# LED.net
KiCad netlist of a schematic drawn in Altium Designer
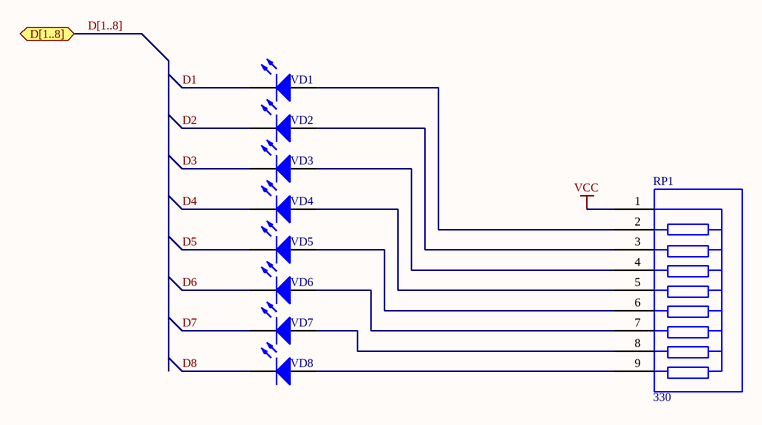
[diagram p0: LED.SchDoc]

(export (version "E")
  (design (tool "Eeschema 10.0.6"))
  (components
    (comp (ref "RP1") (value "330") (footprint "SIP9") (libsource (lib "TEST2024") (part "SIP-A09")))
    (comp (ref "VD1")
      (value "BT101")
      (footprint "LED-5")
      (description "Typical INFRARED GaAs LED")
      (fields (field (name "PUBLISHER") "Altium Limited"))
      (libsource (lib "TEST2024") (part "LED0"))
    )
    (comp (ref "VD2")
      (value "BT101")
      (footprint "LED-5")
      (description "Typical INFRARED GaAs LED")
      (fields (field (name "PUBLISHER") "Altium Limited"))
      (libsource (lib "TEST2024") (part "LED0"))
    )
    (comp (ref "VD3")
      (value "BT101")
      (footprint "LED-5")
      (description "Typical INFRARED GaAs LED")
      (fields (field (name "PUBLISHER") "Altium Limited"))
      (libsource (lib "TEST2024") (part "LED0"))
    )
    (comp (ref "VD4")
      (value "BT101")
      (footprint "LED-5")
      (description "Typical INFRARED GaAs LED")
      (fields (field (name "PUBLISHER") "Altium Limited"))
      (libsource (lib "TEST2024") (part "LED0"))
    )
    (comp (ref "VD5")
      (value "BT101")
      (footprint "LED-5")
      (description "Typical INFRARED GaAs LED")
      (fields (field (name "PUBLISHER") "Altium Limited"))
      (libsource (lib "TEST2024") (part "LED0"))
    )
    (comp (ref "VD6")
      (value "BT101")
      (footprint "LED-5")
      (description "Typical INFRARED GaAs LED")
      (fields (field (name "PUBLISHER") "Altium Limited"))
      (libsource (lib "TEST2024") (part "LED0"))
    )
    (comp (ref "VD7")
      (value "BT101")
      (footprint "LED-5")
      (description "Typical INFRARED GaAs LED")
      (fields (field (name "PUBLISHER") "Altium Limited"))
      (libsource (lib "TEST2024") (part "LED0"))
    )
    (comp (ref "VD8")
      (value "BT101")
      (footprint "LED-5")
      (description "Typical INFRARED GaAs LED")
      (fields (field (name "PUBLISHER") "Altium Limited"))
      (libsource (lib "TEST2024") (part "LED0"))
    )
  )
  (nets
    (net (code "1") (name "/D1") (class "Default")
      (node (ref "VD1") (pin "2") (pinfunction "K_2") (pintype "passive"))
    )
    (net (code "2") (name "/D2") (class "Default")
      (node (ref "VD2") (pin "2") (pinfunction "K_2") (pintype "passive"))
    )
    (net (code "3") (name "/D3") (class "Default")
      (node (ref "VD3") (pin "2") (pinfunction "K_2") (pintype "passive"))
    )
    (net (code "4") (name "/D4") (class "Default")
      (node (ref "VD4") (pin "2") (pinfunction "K_2") (pintype "passive"))
    )
    (net (code "5") (name "/D5") (class "Default")
      (node (ref "VD5") (pin "2") (pinfunction "K_2") (pintype "passive"))
    )
    (net (code "6") (name "/D6") (class "Default")
      (node (ref "VD6") (pin "2") (pinfunction "K_2") (pintype "passive"))
    )
    (net (code "7") (name "/D7") (class "Default")
      (node (ref "VD7") (pin "2") (pinfunction "K_2") (pintype "passive"))
    )
    (net (code "8") (name "/D8") (class "Default")
      (node (ref "VD8") (pin "2") (pinfunction "K_2") (pintype "passive"))
    )
    (net (code "10") (name "Net-(VD1-A)") (class "Default")
      (node (ref "RP1") (pin "2") (pinfunction "2_2") (pintype "power_in"))
      (node (ref "VD1") (pin "1") (pinfunction "A_1") (pintype "passive"))
    )
    (net (code "11") (name "Net-(VD2-A)") (class "Default")
      (node (ref "RP1") (pin "3") (pinfunction "3_3") (pintype "power_in"))
      (node (ref "VD2") (pin "1") (pinfunction "A_1") (pintype "passive"))
    )
    (net (code "12") (name "Net-(VD3-A)") (class "Default")
      (node (ref "RP1") (pin "4") (pinfunction "4_4") (pintype "power_in"))
      (node (ref "VD3") (pin "1") (pinfunction "A_1") (pintype "passive"))
    )
    (net (code "13") (name "Net-(VD4-A)") (class "Default")
      (node (ref "RP1") (pin "5") (pinfunction "5_5") (pintype "power_in"))
      (node (ref "VD4") (pin "1") (pinfunction "A_1") (pintype "passive"))
    )
    (net (code "14") (name "Net-(VD5-A)") (class "Default")
      (node (ref "RP1") (pin "6") (pinfunction "6_6") (pintype "power_in"))
      (node (ref "VD5") (pin "1") (pinfunction "A_1") (pintype "passive"))
    )
    (net (code "15") (name "Net-(VD6-A)") (class "Default")
      (node (ref "RP1") (pin "7") (pinfunction "7_7") (pintype "power_in"))
      (node (ref "VD6") (pin "1") (pinfunction "A_1") (pintype "passive"))
    )
    (net (code "16") (name "Net-(VD7-A)") (class "Default")
      (node (ref "RP1") (pin "8") (pinfunction "8_8") (pintype "power_in"))
      (node (ref "VD7") (pin "1") (pinfunction "A_1") (pintype "passive"))
    )
    (net (code "17") (name "Net-(VD8-A)") (class "Default")
      (node (ref "RP1") (pin "9") (pinfunction "9_9") (pintype "power_in"))
      (node (ref "VD8") (pin "1") (pinfunction "A_1") (pintype "passive"))
    )
    (net (code "18") (name "VCC") (class "Default")
      (node (ref "RP1") (pin "1") (pinfunction "1_1") (pintype "power_in"))
    )
  )
)
